# Button.net
KiCad netlist of a schematic drawn in Altium Designer
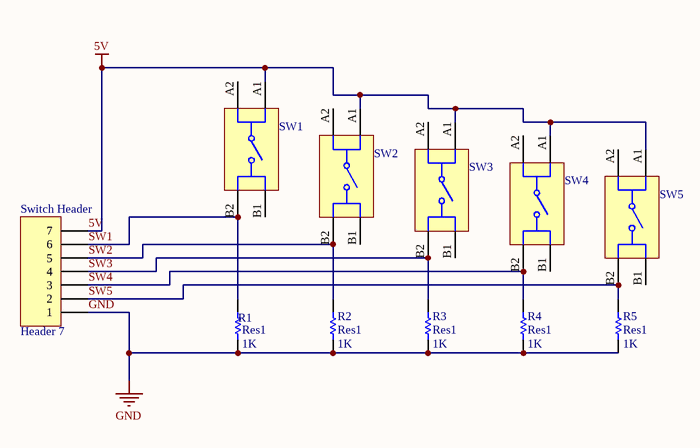
[diagram p0: Button.SchDoc]

(export (version "E")
  (design (tool "Eeschema 10.0.6"))
  (components
    (comp (ref "R1")
      (value "Res1")
      (footprint "AXIAL-0.3")
      (description "Resistor")
      (fields (field (name "ALTIUM_VALUE") "1K") (field (name "PUBLISHER") "Altium Limited"))
      (libsource (lib "Miscellaneous Devices") (part "Res1"))
    )
    (comp (ref "R2")
      (value "Res1")
      (footprint "AXIAL-0.3")
      (description "Resistor")
      (fields (field (name "ALTIUM_VALUE") "1K") (field (name "PUBLISHER") "Altium Limited"))
      (libsource (lib "Miscellaneous Devices") (part "Res1"))
    )
    (comp (ref "R3")
      (value "Res1")
      (footprint "AXIAL-0.3")
      (description "Resistor")
      (fields (field (name "ALTIUM_VALUE") "1K") (field (name "PUBLISHER") "Altium Limited"))
      (libsource (lib "Miscellaneous Devices") (part "Res1"))
    )
    (comp (ref "R4")
      (value "Res1")
      (footprint "AXIAL-0.3")
      (description "Resistor")
      (fields (field (name "ALTIUM_VALUE") "1K") (field (name "PUBLISHER") "Altium Limited"))
      (libsource (lib "Miscellaneous Devices") (part "Res1"))
    )
    (comp (ref "R5")
      (value "Res1")
      (footprint "AXIAL-0.3")
      (description "Resistor")
      (fields (field (name "ALTIUM_VALUE") "1K") (field (name "PUBLISHER") "Altium Limited"))
      (libsource (lib "Miscellaneous Devices") (part "Res1"))
    )
    (comp (ref "SW1")
      (value "430172073816")
      (footprint "WS-TASV_L12W12H7.3_4301x20738x6")
      (description "WS-TASV SMT Tact Switch, L12 x W12 x H7.3mm, 160g, SPST-NO, 12V, 50mA")
      (fields (field (name "MANUFACTURER") "Wurth Elektronik"))
      (libsource (lib "Altium_WS-TASV (rev22c)") (part "430172073816"))
    )
    (comp (ref "SW2")
      (value "430172073816")
      (footprint "WS-TASV_L12W12H7.3_4301x20738x6")
      (description "WS-TASV SMT Tact Switch, L12 x W12 x H7.3mm, 160g, SPST-NO, 12V, 50mA")
      (fields (field (name "MANUFACTURER") "Wurth Elektronik"))
      (libsource (lib "Altium_WS-TASV (rev22c)") (part "430172073816"))
    )
    (comp (ref "SW3")
      (value "430172073816")
      (footprint "WS-TASV_L12W12H7.3_4301x20738x6")
      (description "WS-TASV SMT Tact Switch, L12 x W12 x H7.3mm, 160g, SPST-NO, 12V, 50mA")
      (fields (field (name "MANUFACTURER") "Wurth Elektronik"))
      (libsource (lib "Altium_WS-TASV (rev22c)") (part "430172073816"))
    )
    (comp (ref "SW4")
      (value "430172073816")
      (footprint "WS-TASV_L12W12H7.3_4301x20738x6")
      (description "WS-TASV SMT Tact Switch, L12 x W12 x H7.3mm, 160g, SPST-NO, 12V, 50mA")
      (fields (field (name "MANUFACTURER") "Wurth Elektronik"))
      (libsource (lib "Altium_WS-TASV (rev22c)") (part "430172073816"))
    )
    (comp (ref "SW5")
      (value "430172073816")
      (footprint "WS-TASV_L12W12H7.3_4301x20738x6")
      (description "WS-TASV SMT Tact Switch, L12 x W12 x H7.3mm, 160g, SPST-NO, 12V, 50mA")
      (fields (field (name "MANUFACTURER") "Wurth Elektronik"))
      (libsource (lib "Altium_WS-TASV (rev22c)") (part "430172073816"))
    )
    (comp (ref "Switch Header")
      (value "Header 7")
      (footprint "HDR1X7")
      (description "Header, 7-Pin")
      (fields (field (name "PUBLISHER") "Altium Limited"))
      (libsource (lib "Miscellaneous Connectors") (part "Header 7"))
    )
  )
  (nets
    (net (code "1") (name "/SW1") (class "Default")
      (node (ref "R1") (pin "1") (pinfunction "1_1") (pintype "passive"))
      (node (ref "SW1") (pin "B2") (pinfunction "B2_B2") (pintype "passive"))
      (node (ref "Switch Header") (pin "6") (pinfunction "6_6") (pintype "passive"))
    )
    (net (code "2") (name "/SW2") (class "Default")
      (node (ref "R2") (pin "1") (pinfunction "1_1") (pintype "passive"))
      (node (ref "SW2") (pin "B2") (pinfunction "B2_B2") (pintype "passive"))
      (node (ref "Switch Header") (pin "5") (pinfunction "5_5") (pintype "passive"))
    )
    (net (code "3") (name "/SW3") (class "Default")
      (node (ref "R3") (pin "1") (pinfunction "1_1") (pintype "passive"))
      (node (ref "SW3") (pin "B2") (pinfunction "B2_B2") (pintype "passive"))
      (node (ref "Switch Header") (pin "4") (pinfunction "4_4") (pintype "passive"))
    )
    (net (code "4") (name "/SW4") (class "Default")
      (node (ref "R4") (pin "1") (pinfunction "1_1") (pintype "passive"))
      (node (ref "SW4") (pin "B2") (pinfunction "B2_B2") (pintype "passive"))
      (node (ref "Switch Header") (pin "3") (pinfunction "3_3") (pintype "passive"))
    )
    (net (code "5") (name "/SW5") (class "Default")
      (node (ref "R5") (pin "1") (pinfunction "1_1") (pintype "passive"))
      (node (ref "SW5") (pin "B2") (pinfunction "B2_B2") (pintype "passive"))
      (node (ref "Switch Header") (pin "2") (pinfunction "2_2") (pintype "passive"))
    )
    (net (code "6") (name "5V") (class "Default")
      (node (ref "SW1") (pin "A1") (pinfunction "A1_A1") (pintype "passive"))
      (node (ref "SW2") (pin "A1") (pinfunction "A1_A1") (pintype "passive"))
      (node (ref "SW3") (pin "A1") (pinfunction "A1_A1") (pintype "passive"))
      (node (ref "SW4") (pin "A1") (pinfunction "A1_A1") (pintype "passive"))
      (node (ref "SW5") (pin "A1") (pinfunction "A1_A1") (pintype "passive"))
      (node (ref "Switch Header") (pin "7") (pinfunction "7_7") (pintype "passive"))
    )
    (net (code "7") (name "GND") (class "Default")
      (node (ref "R1") (pin "2") (pinfunction "2_2") (pintype "passive"))
      (node (ref "R2") (pin "2") (pinfunction "2_2") (pintype "passive"))
      (node (ref "R3") (pin "2") (pinfunction "2_2") (pintype "passive"))
      (node (ref "R4") (pin "2") (pinfunction "2_2") (pintype "passive"))
      (node (ref "R5") (pin "2") (pinfunction "2_2") (pintype "passive"))
      (node (ref "Switch Header") (pin "1") (pinfunction "1_1") (pintype "passive"))
    )
    (net (code "8") (name "unconnected-(SW1-PadA2)") (class "Default")
      (node (ref "SW1") (pin "A2") (pinfunction "A2_A2") (pintype "passive"))
    )
    (net (code "9") (name "unconnected-(SW1-PadB1)") (class "Default")
      (node (ref "SW1") (pin "B1") (pinfunction "B1_B1") (pintype "passive"))
    )
    (net (code "10") (name "unconnected-(SW2-PadA2)") (class "Default")
      (node (ref "SW2") (pin "A2") (pinfunction "A2_A2") (pintype "passive"))
    )
    (net (code "11") (name "unconnected-(SW2-PadB1)") (class "Default")
      (node (ref "SW2") (pin "B1") (pinfunction "B1_B1") (pintype "passive"))
    )
    (net (code "12") (name "unconnected-(SW3-PadA2)") (class "Default")
      (node (ref "SW3") (pin "A2") (pinfunction "A2_A2") (pintype "passive"))
    )
    (net (code "13") (name "unconnected-(SW3-PadB1)") (class "Default")
      (node (ref "SW3") (pin "B1") (pinfunction "B1_B1") (pintype "passive"))
    )
    (net (code "14") (name "unconnected-(SW4-PadA2)") (class "Default")
      (node (ref "SW4") (pin "A2") (pinfunction "A2_A2") (pintype "passive"))
    )
    (net (code "15") (name "unconnected-(SW4-PadB1)") (class "Default")
      (node (ref "SW4") (pin "B1") (pinfunction "B1_B1") (pintype "passive"))
    )
    (net (code "16") (name "unconnected-(SW5-PadA2)") (class "Default")
      (node (ref "SW5") (pin "A2") (pinfunction "A2_A2") (pintype "passive"))
    )
    (net (code "17") (name "unconnected-(SW5-PadB1)") (class "Default")
      (node (ref "SW5") (pin "B1") (pinfunction "B1_B1") (pintype "passive"))
    )
  )
)
